# divers.net
KiCad netlist of a schematic drawn in Altium Designer
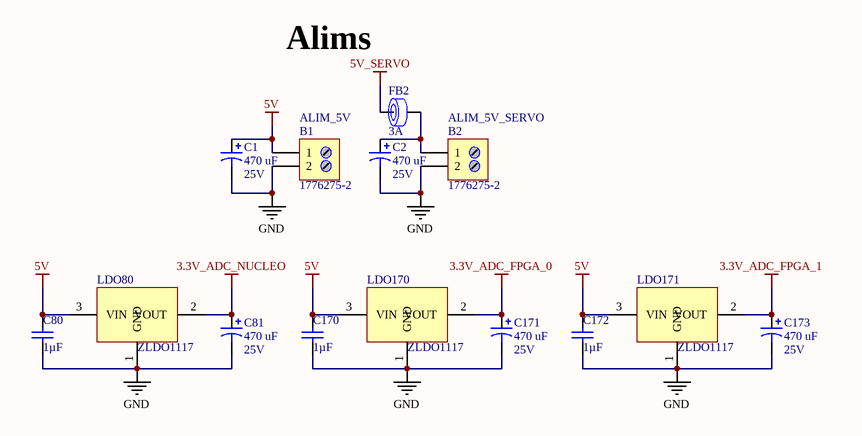
[diagram p0: divers.SchDoc]

(export (version "E")
  (design (tool "Eeschema 10.0.6"))
  (components
    (comp (ref "B1")
      (value "1776275-2")
      (footprint "BORNIER_2V_3.5MM")
      (description "TERM BLOCK 2POS SIDE ENT 3.5MM")
      (fields (field (name "MANUFACTURER") "TE Connectivity AMP Connectors"))
      (libsource (lib "Divers") (part "1776275-2"))
    )
    (comp (ref "B2")
      (value "1776275-2")
      (footprint "BORNIER_2V_3.5MM")
      (description "TERM BLOCK 2POS SIDE ENT 3.5MM")
      (fields (field (name "MANUFACTURER") "TE Connectivity AMP Connectors"))
      (libsource (lib "Divers") (part "1776275-2"))
    )
    (comp (ref "C1")
      (value "470 uF")
      (footprint "WCAP-ATG8_8x11.5x3.5x0.5")
      (description "CAP Alu 470 UF 20% 25 V")
      (fields
        (field (name "MANUFACTURER") "Wurth Elektronik")
        (field (name "MANUFACTURER PART NUMBER") "860010474013")
        (field (name "RATEDVOLTAGE") "25V")
      )
      (libsource (lib "Condensateur") (part "WCAP-ATG8, 860010474013"))
    )
    (comp (ref "C2")
      (value "470 uF")
      (footprint "WCAP-ATG8_8x11.5x3.5x0.5")
      (description "CAP Alu 470 UF 20% 25 V")
      (fields
        (field (name "MANUFACTURER") "Wurth Elektronik")
        (field (name "MANUFACTURER PART NUMBER") "860010474013")
        (field (name "RATEDVOLTAGE") "25V")
      )
      (libsource (lib "Condensateur") (part "WCAP-ATG8, 860010474013"))
    )
    (comp (ref "C80")
      (value "1µF")
      (footprint "WCAP-CSGP_0603, 1.6x0.8x0.8")
      (description "CAP CER 100nF 50V X7R 0603")
      (fields
        (field (name "MANUFACTURER") "Wurth Elektronik")
        (field (name "MANUFACTURER PART NUMBER") "885012206095")
      )
      (libsource (lib "Condensateur") (part "WCAP-CSGP, 885012206095"))
    )
    (comp (ref "C81")
      (value "470 uF")
      (footprint "WCAP-ATG8_8x11.5x3.5x0.5")
      (description "CAP Alu 470 UF 20% 25 V")
      (fields
        (field (name "MANUFACTURER") "Wurth Elektronik")
        (field (name "MANUFACTURER PART NUMBER") "860010474013")
        (field (name "RATEDVOLTAGE") "25V")
      )
      (libsource (lib "Condensateur") (part "WCAP-ATG8, 860010474013"))
    )
    (comp (ref "C170")
      (value "1µF")
      (footprint "WCAP-CSGP_0603, 1.6x0.8x0.8")
      (description "CAP CER 100nF 50V X7R 0603")
      (fields
        (field (name "MANUFACTURER") "Wurth Elektronik")
        (field (name "MANUFACTURER PART NUMBER") "885012206095")
      )
      (libsource (lib "Condensateur") (part "WCAP-CSGP, 885012206095"))
    )
    (comp (ref "C171")
      (value "470 uF")
      (footprint "WCAP-ATG8_8x11.5x3.5x0.5")
      (description "CAP Alu 470 UF 20% 25 V")
      (fields
        (field (name "MANUFACTURER") "Wurth Elektronik")
        (field (name "MANUFACTURER PART NUMBER") "860010474013")
        (field (name "RATEDVOLTAGE") "25V")
      )
      (libsource (lib "Condensateur") (part "WCAP-ATG8, 860010474013"))
    )
    (comp (ref "C172")
      (value "1µF")
      (footprint "WCAP-CSGP_0603, 1.6x0.8x0.8")
      (description "CAP CER 100nF 50V X7R 0603")
      (fields
        (field (name "MANUFACTURER") "Wurth Elektronik")
        (field (name "MANUFACTURER PART NUMBER") "885012206095")
      )
      (libsource (lib "Condensateur") (part "WCAP-CSGP, 885012206095"))
    )
    (comp (ref "C173")
      (value "470 uF")
      (footprint "WCAP-ATG8_8x11.5x3.5x0.5")
      (description "CAP Alu 470 UF 20% 25 V")
      (fields
        (field (name "MANUFACTURER") "Wurth Elektronik")
        (field (name "MANUFACTURER PART NUMBER") "860010474013")
        (field (name "RATEDVOLTAGE") "25V")
      )
      (libsource (lib "Condensateur") (part "WCAP-ATG8, 860010474013"))
    )
    (comp (ref "FB2")
      (value "742792023")
      (footprint "WE-CBF_0805_High Current")
      (description "Ferrite Bead 120ohm 0805 max3.0A")
      (fields (field (name "MANUFACTURER") "Wurth Elektronik") (field (name "RATEDCURRENT") "3A"))
      (libsource (lib "Inductance") (part "WE-CBF, 742792023"))
    )
    (comp (ref "LDO80")
      (value "ZLDO1117")
      (footprint "Divers_goldo:SOT223_M")
      (fields (field (name "MANUFACTURER") "Diodes Incorporated"))
      (libsource (lib "Divers_goldo") (part "ZLDO1117"))
    )
    (comp (ref "LDO170")
      (value "ZLDO1117")
      (footprint "Divers_goldo:SOT223_M")
      (fields (field (name "MANUFACTURER") "Diodes Incorporated"))
      (libsource (lib "Divers_goldo") (part "ZLDO1117"))
    )
    (comp (ref "LDO171")
      (value "ZLDO1117")
      (footprint "Divers_goldo:SOT223_M")
      (fields (field (name "MANUFACTURER") "Diodes Incorporated"))
      (libsource (lib "Divers_goldo") (part "ZLDO1117"))
    )
  )
  (nets
    (net (code "1") (name "3.3V_ADC_FPGA_0") (class "Default")
      (node (ref "C171") (pin "1") (pinfunction "1_1") (pintype "passive"))
      (node (ref "LDO170") (pin "2") (pinfunction "VOUT_2") (pintype "power_in"))
    )
    (net (code "2") (name "3.3V_ADC_FPGA_1") (class "Default")
      (node (ref "C173") (pin "1") (pinfunction "1_1") (pintype "passive"))
      (node (ref "LDO171") (pin "2") (pinfunction "VOUT_2") (pintype "power_in"))
    )
    (net (code "3") (name "3.3V_ADC_NUCLEO") (class "Default")
      (node (ref "C81") (pin "1") (pinfunction "1_1") (pintype "passive"))
      (node (ref "LDO80") (pin "2") (pinfunction "VOUT_2") (pintype "power_in"))
    )
    (net (code "4") (name "5V") (class "Default")
      (node (ref "B1") (pin "1") (pinfunction "1_1") (pintype "passive"))
      (node (ref "C1") (pin "1") (pinfunction "1_1") (pintype "passive"))
      (node (ref "C170") (pin "1") (pinfunction "1_1") (pintype "passive"))
      (node (ref "C172") (pin "1") (pinfunction "1_1") (pintype "passive"))
      (node (ref "C80") (pin "1") (pinfunction "1_1") (pintype "passive"))
      (node (ref "LDO170") (pin "3") (pinfunction "VIN_3") (pintype "power_in"))
      (node (ref "LDO171") (pin "3") (pinfunction "VIN_3") (pintype "power_in"))
      (node (ref "LDO80") (pin "3") (pinfunction "VIN_3") (pintype "power_in"))
    )
    (net (code "5") (name "5V_SERVO") (class "Default")
      (node (ref "FB2") (pin "1") (pinfunction "1_1") (pintype "passive"))
    )
    (net (code "6") (name "GND") (class "Default")
      (node (ref "B1") (pin "2") (pinfunction "2_2") (pintype "passive"))
      (node (ref "B2") (pin "2") (pinfunction "2_2") (pintype "passive"))
      (node (ref "C1") (pin "2") (pinfunction "2_2") (pintype "passive"))
      (node (ref "C170") (pin "2") (pinfunction "2_2") (pintype "passive"))
      (node (ref "C171") (pin "2") (pinfunction "2_2") (pintype "passive"))
      (node (ref "C172") (pin "2") (pinfunction "2_2") (pintype "passive"))
      (node (ref "C173") (pin "2") (pinfunction "2_2") (pintype "passive"))
      (node (ref "C2") (pin "2") (pinfunction "2_2") (pintype "passive"))
      (node (ref "C80") (pin "2") (pinfunction "2_2") (pintype "passive"))
      (node (ref "C81") (pin "2") (pinfunction "2_2") (pintype "passive"))
      (node (ref "LDO170") (pin "1") (pinfunction "GND_1") (pintype "power_in"))
      (node (ref "LDO171") (pin "1") (pinfunction "GND_1") (pintype "power_in"))
      (node (ref "LDO80") (pin "1") (pinfunction "GND_1") (pintype "power_in"))
    )
    (net (code "7") (name "Net-(B2-Pad1)") (class "Default")
      (node (ref "B2") (pin "1") (pinfunction "1_1") (pintype "passive"))
      (node (ref "C2") (pin "1") (pinfunction "1_1") (pintype "passive"))
      (node (ref "FB2") (pin "2") (pinfunction "2_2") (pintype "passive"))
    )
  )
)
